# EmonESP.net
KiCad netlist of a schematic drawn in EAGLE
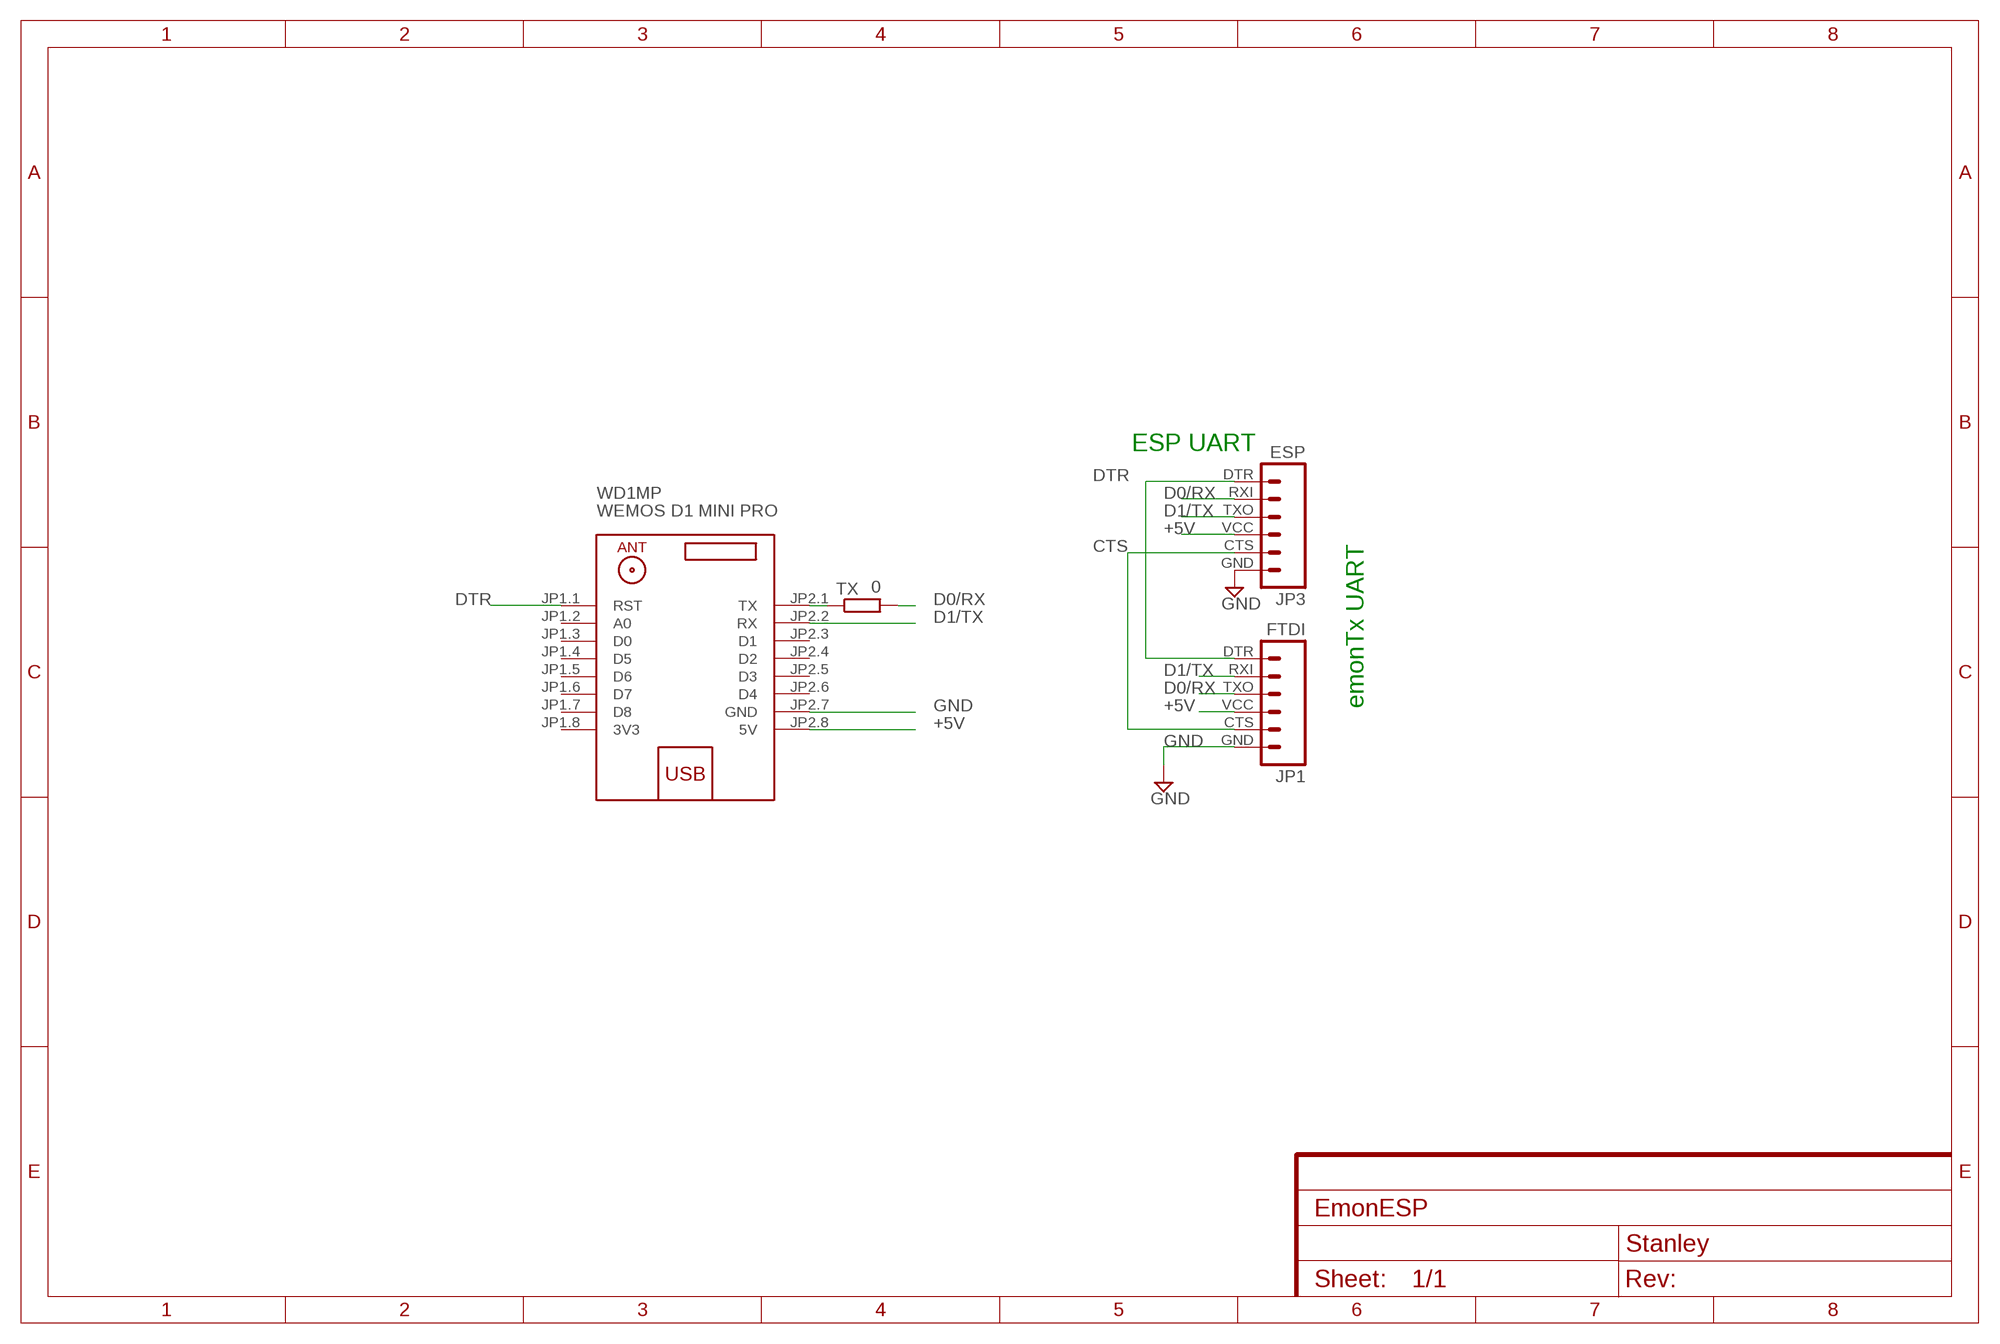
[diagram p0: schematic, sheet 1]

(export (version "E")
  (design (tool "Eeschema 10.0.6"))
  (components
    (comp (ref "JP1")
      (value "FTDI")
      (footprint "eagle-import:FTDI_BASIC")
      (libsource (lib "eagle-import") (part "FTDI_BASICPTH"))
    )
    (comp (ref "JP3")
      (value "ESP")
      (footprint "eagle-import:FTDI_BASIC")
      (libsource (lib "eagle-import") (part "FTDI_BASICPTH"))
    )
    (comp (ref "TX")
      (value "0")
      (footprint "eagle-import:R0603")
      (libsource (lib "eagle-import") (part "R-EU_R0603"))
    )
    (comp (ref "WD1MP")
      (value "WEMOS D1 MINI PRO")
      (footprint "eagle-import:WEMOS-D1-MINI-PRO")
      (libsource (lib "eagle-import") (part "WEMOS-D1-MINI-PRO"))
    )
  )
  (nets
    (net (code "1") (name "/+5V") (class "Default")
      (node (ref "JP1") (pin "VCC") (pinfunction "4_VCC") (pintype "passive"))
      (node (ref "JP3") (pin "VCC") (pinfunction "4_VCC") (pintype "passive"))
      (node (ref "WD1MP") (pin "JP2.8") (pinfunction "5V_JP2.8") (pintype "power_in"))
    )
    (net (code "2") (name "/3V3") (class "Default")
      (node (ref "WD1MP") (pin "JP1.8") (pinfunction "3V3_JP1.8") (pintype "power_in"))
    )
    (net (code "3") (name "/CTS") (class "Default")
      (node (ref "JP1") (pin "CTS") (pinfunction "5_CTS") (pintype "passive"))
      (node (ref "JP3") (pin "CTS") (pinfunction "5_CTS") (pintype "passive"))
    )
    (net (code "4") (name "/D0{slash}RX") (class "Default")
      (node (ref "JP1") (pin "TXO") (pinfunction "3_TXO") (pintype "passive"))
      (node (ref "JP3") (pin "RXI") (pinfunction "2_RXI") (pintype "passive"))
      (node (ref "TX") (pin "2") (pinfunction "2_2") (pintype "passive"))
    )
    (net (code "5") (name "/D1{slash}TX") (class "Default")
      (node (ref "JP1") (pin "RXI") (pinfunction "2_RXI") (pintype "passive"))
      (node (ref "JP3") (pin "TXO") (pinfunction "3_TXO") (pintype "passive"))
      (node (ref "WD1MP") (pin "JP2.2") (pinfunction "RX_JP2.2") (pintype "bidirectional"))
    )
    (net (code "6") (name "/DTR") (class "Default")
      (node (ref "JP1") (pin "DTR") (pinfunction "1_DTR") (pintype "passive"))
      (node (ref "JP3") (pin "DTR") (pinfunction "1_DTR") (pintype "passive"))
      (node (ref "WD1MP") (pin "JP1.1") (pinfunction "RST_JP1.1") (pintype "bidirectional"))
    )
    (net (code "7") (name "GND") (class "Default")
      (node (ref "JP1") (pin "GND") (pinfunction "6_GND") (pintype "passive"))
      (node (ref "JP3") (pin "GND") (pinfunction "6_GND") (pintype "passive"))
      (node (ref "WD1MP") (pin "JP2.7") (pinfunction "GND_JP2.7") (pintype "power_in"))
    )
    (net (code "8") (name "Net-(WD1MP-TX)") (class "Default")
      (node (ref "TX") (pin "1") (pinfunction "1_1") (pintype "passive"))
      (node (ref "WD1MP") (pin "JP2.1") (pinfunction "TX_JP2.1") (pintype "bidirectional"))
    )
    (net (code "9") (name "unconnected-(WD1MP-A0-PadJP1.2)") (class "Default")
      (node (ref "WD1MP") (pin "JP1.2") (pinfunction "A0_JP1.2") (pintype "bidirectional"))
    )
    (net (code "10") (name "unconnected-(WD1MP-D0-PadJP1.3)") (class "Default")
      (node (ref "WD1MP") (pin "JP1.3") (pinfunction "D0_JP1.3") (pintype "bidirectional"))
    )
    (net (code "11") (name "unconnected-(WD1MP-D1-PadJP2.3)") (class "Default")
      (node (ref "WD1MP") (pin "JP2.3") (pinfunction "D1_JP2.3") (pintype "bidirectional"))
    )
    (net (code "12") (name "unconnected-(WD1MP-D2-PadJP2.4)") (class "Default")
      (node (ref "WD1MP") (pin "JP2.4") (pinfunction "D2_JP2.4") (pintype "bidirectional"))
    )
    (net (code "13") (name "unconnected-(WD1MP-D3-PadJP2.5)") (class "Default")
      (node (ref "WD1MP") (pin "JP2.5") (pinfunction "D3_JP2.5") (pintype "bidirectional"))
    )
    (net (code "14") (name "unconnected-(WD1MP-D4-PadJP2.6)") (class "Default")
      (node (ref "WD1MP") (pin "JP2.6") (pinfunction "D4_JP2.6") (pintype "bidirectional"))
    )
    (net (code "15") (name "unconnected-(WD1MP-D5-PadJP1.4)") (class "Default")
      (node (ref "WD1MP") (pin "JP1.4") (pinfunction "D5_JP1.4") (pintype "bidirectional"))
    )
    (net (code "16") (name "unconnected-(WD1MP-D6-PadJP1.5)") (class "Default")
      (node (ref "WD1MP") (pin "JP1.5") (pinfunction "D6_JP1.5") (pintype "bidirectional"))
    )
    (net (code "17") (name "unconnected-(WD1MP-D7-PadJP1.6)") (class "Default")
      (node (ref "WD1MP") (pin "JP1.6") (pinfunction "D7_JP1.6") (pintype "bidirectional"))
    )
    (net (code "18") (name "unconnected-(WD1MP-D8-PadJP1.7)") (class "Default")
      (node (ref "WD1MP") (pin "JP1.7") (pinfunction "D8_JP1.7") (pintype "bidirectional"))
    )
  )
)
